# 6_TS.net
KiCad netlist of a schematic drawn in Altium Designer
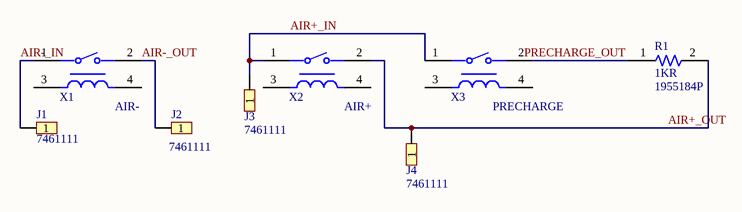
[diagram p0: [6]TS.SchDoc]

(export (version "E")
  (design (tool "Eeschema 10.0.6"))
  (components
    (comp (ref "J1")
      (value "7461111")
      (footprint "J_Power_Connector_180A")
      (libsource (lib "") (part "J_Power_Connector_180A_1"))
    )
    (comp (ref "J2")
      (value "7461111")
      (footprint "J_Power_Connector_180A")
      (libsource (lib "") (part "J_Power_Connector_180A_1"))
    )
    (comp (ref "J3")
      (value "7461111")
      (footprint "J_Power_Connector_180A")
      (libsource (lib "Electromechanical") (part "J_Power_Connector_180A"))
    )
    (comp (ref "J4")
      (value "7461111")
      (footprint "J_Power_Connector_180A")
      (libsource (lib "Electromechanical") (part "J_Power_Connector_180A"))
    )
    (comp (ref "R1")
      (value "R470-TO247")
      (footprint "RTO247")
      (description "Res, 1K, 100W, To-247, Thick Film Rohs Compliant: Yes ¦Cgs Te Connectivity MPT100C1K0F")
      (fields
        (field (name "MANUFACTURER") "TE Connectivity")
        (field (name "MANUFACTURER PART NUMBER") "MPT100C470RF")
        (field (name "RESISTANCE") "1KR")
        (field (name "SUPPLIER PART NUMBER 1") "1955184P")
      )
      (libsource (lib "Passives") (part "R1K-TO247"))
    )
    (comp (ref "X1")
      (value "AIR-")
      (footprint "RELAY_LEV100H")
      (description "Electromechanical Relay 12VDC 26Ohm 100A SPST-NO-DM(57.96x40.77)mm Chassis Contactor Relay")
      (fields (field (name "MANUFACTURER") "Cynergy3") (field (name "MANUFACTURER PART NUMBER") "DAR72410FU"))
      (libsource (lib "Electromechanical") (part "Relay_LEV100H"))
    )
    (comp (ref "X2")
      (value "AIR+")
      (footprint "RELAY_LEV100H")
      (description "Electromechanical Relay 12VDC 26Ohm 100A SPST-NO-DM(57.96x40.77)mm Chassis Contactor Relay")
      (fields (field (name "MANUFACTURER") "Cynergy3") (field (name "MANUFACTURER PART NUMBER") "DAR72410FU"))
      (libsource (lib "Electromechanical") (part "Relay_LEV100H"))
    )
    (comp (ref "X3")
      (value "PRECHARGE")
      (footprint "RELAY_LEV100H")
      (description "Electromechanical Relay 12VDC 26Ohm 100A SPST-NO-DM(57.96x40.77)mm Chassis Contactor Relay")
      (fields (field (name "MANUFACTURER") "Cynergy3") (field (name "MANUFACTURER PART NUMBER") "DAR72410FU"))
      (libsource (lib "Electromechanical") (part "Relay_LEV100H"))
    )
  )
  (nets
    (net (code "1") (name "/AIR+_IN") (class "Default")
      (node (ref "J3") (pin "1") (pinfunction "1_1") (pintype "passive"))
      (node (ref "X2") (pin "1") (pinfunction "1_1") (pintype "passive"))
      (node (ref "X3") (pin "1") (pinfunction "1_1") (pintype "passive"))
    )
    (net (code "2") (name "/AIR+_OUT") (class "Default")
      (node (ref "J4") (pin "1") (pinfunction "1_1") (pintype "passive"))
      (node (ref "R1") (pin "2") (pinfunction "2_2") (pintype "passive"))
      (node (ref "X2") (pin "2") (pinfunction "2_2") (pintype "passive"))
    )
    (net (code "3") (name "/AIR-_IN") (class "Default")
      (node (ref "J1") (pin "1") (pinfunction "1_1") (pintype "passive"))
      (node (ref "X1") (pin "1") (pinfunction "1_1") (pintype "passive"))
    )
    (net (code "4") (name "/AIR-_OUT") (class "Default")
      (node (ref "J2") (pin "1") (pinfunction "1_1") (pintype "passive"))
      (node (ref "X1") (pin "2") (pinfunction "2_2") (pintype "passive"))
    )
    (net (code "5") (name "/PRECHARGE_OUT") (class "Default")
      (node (ref "R1") (pin "1") (pinfunction "1_1") (pintype "passive"))
      (node (ref "X3") (pin "2") (pinfunction "2_2") (pintype "passive"))
    )
    (net (code "6") (name "unconnected-(X1-Pad3)") (class "Default")
      (node (ref "X1") (pin "3") (pinfunction "3_3") (pintype "passive"))
    )
    (net (code "7") (name "unconnected-(X1-Pad4)") (class "Default")
      (node (ref "X1") (pin "4") (pinfunction "4_4") (pintype "passive"))
    )
    (net (code "8") (name "unconnected-(X2-Pad3)") (class "Default")
      (node (ref "X2") (pin "3") (pinfunction "3_3") (pintype "passive"))
    )
    (net (code "9") (name "unconnected-(X2-Pad4)") (class "Default")
      (node (ref "X2") (pin "4") (pinfunction "4_4") (pintype "passive"))
    )
    (net (code "10") (name "unconnected-(X3-Pad3)") (class "Default")
      (node (ref "X3") (pin "3") (pinfunction "3_3") (pintype "passive"))
    )
    (net (code "11") (name "unconnected-(X3-Pad4)") (class "Default")
      (node (ref "X3") (pin "4") (pinfunction "4_4") (pintype "passive"))
    )
  )
)
